# Digital_Output_LED_Monitor.net
KiCad netlist of a schematic drawn in Altium Designer
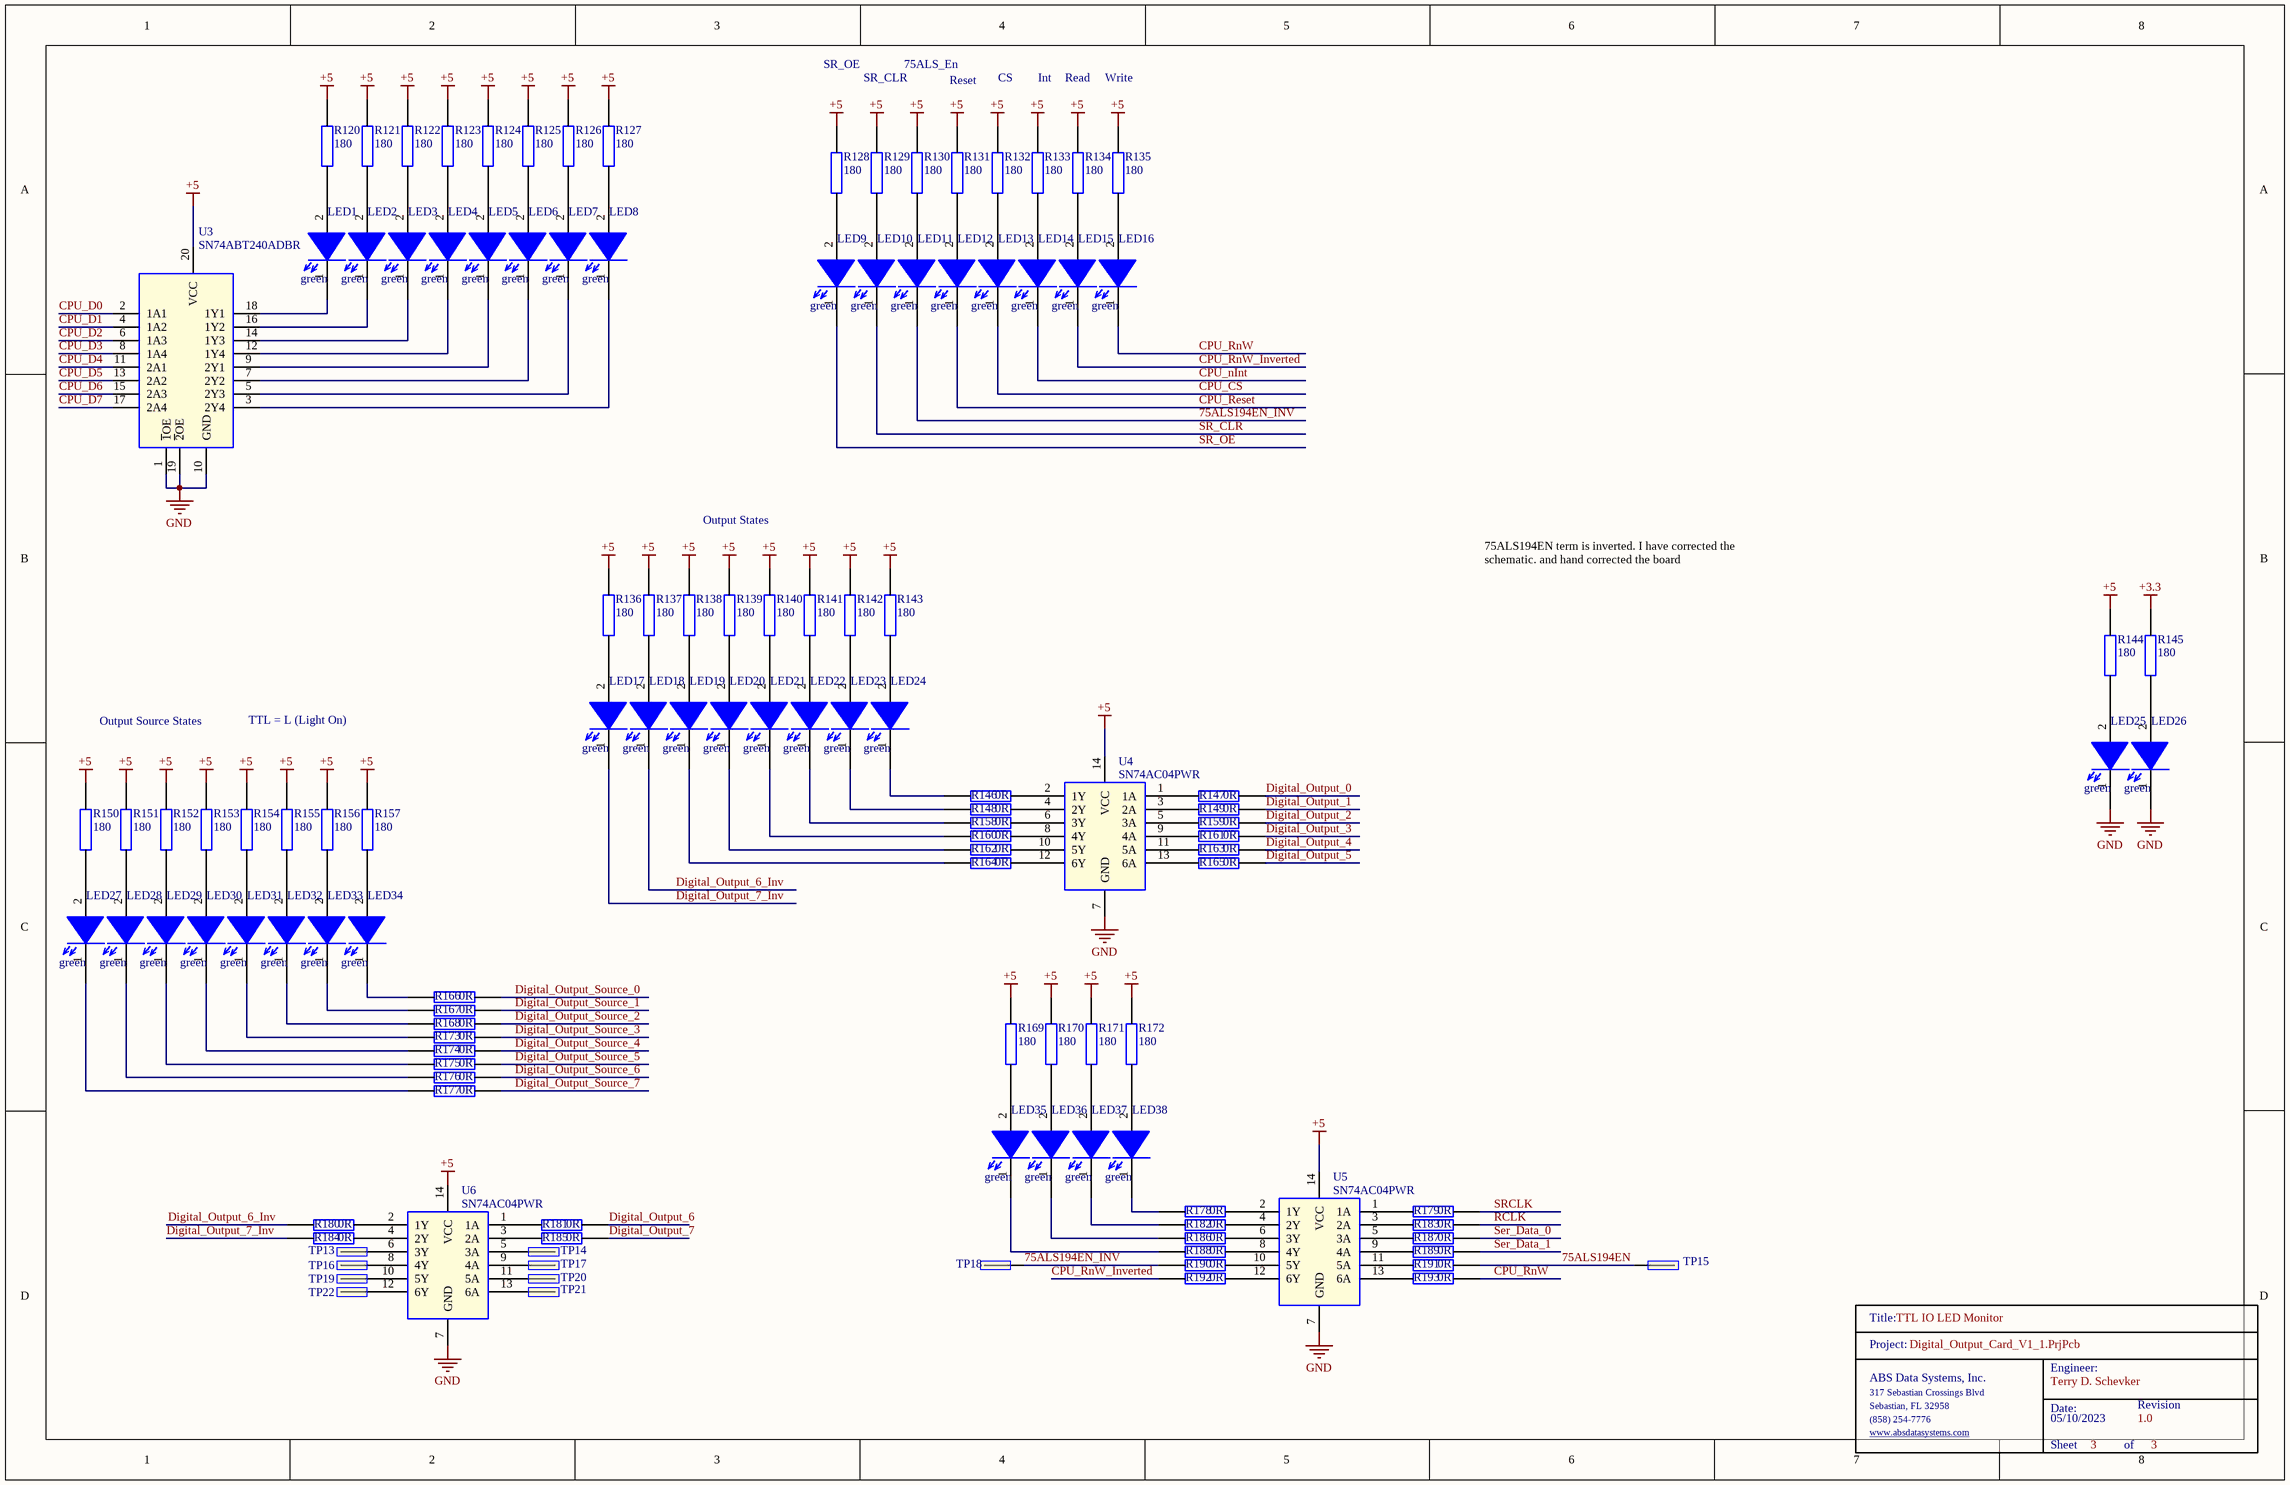
[diagram p0: Digital_Output_LED_Monitor.SchDoc]

(export (version "E")
  (design (tool "Eeschema 10.0.6"))
  (components
    (comp (ref "LED1")
      (value "green")
      (footprint "0603_Diode")
      (description "Wurth Elektronik 0603 green")
      (fields
        (field (name "MANUFACTURER") "Wurth Electronics")
        (field (name "MANUFACTURER PART NUMBER") "150060GS75000")
      )
      (libsource (lib "Misc") (part "150060GS75000"))
    )
    (comp (ref "LED2")
      (value "green")
      (footprint "0603_Diode")
      (description "Wurth Elektronik 0603 green")
      (fields
        (field (name "MANUFACTURER") "Wurth Electronics")
        (field (name "MANUFACTURER PART NUMBER") "150060GS75000")
      )
      (libsource (lib "Misc") (part "150060GS75000"))
    )
    (comp (ref "LED3")
      (value "green")
      (footprint "0603_Diode")
      (description "Wurth Elektronik 0603 green")
      (fields
        (field (name "MANUFACTURER") "Wurth Electronics")
        (field (name "MANUFACTURER PART NUMBER") "150060GS75000")
      )
      (libsource (lib "Misc") (part "150060GS75000"))
    )
    (comp (ref "LED4")
      (value "green")
      (footprint "0603_Diode")
      (description "Wurth Elektronik 0603 green")
      (fields
        (field (name "MANUFACTURER") "Wurth Electronics")
        (field (name "MANUFACTURER PART NUMBER") "150060GS75000")
      )
      (libsource (lib "Misc") (part "150060GS75000"))
    )
    (comp (ref "LED5")
      (value "green")
      (footprint "0603_Diode")
      (description "Wurth Elektronik 0603 green")
      (fields
        (field (name "MANUFACTURER") "Wurth Electronics")
        (field (name "MANUFACTURER PART NUMBER") "150060GS75000")
      )
      (libsource (lib "Misc") (part "150060GS75000"))
    )
    (comp (ref "LED6")
      (value "green")
      (footprint "0603_Diode")
      (description "Wurth Elektronik 0603 green")
      (fields
        (field (name "MANUFACTURER") "Wurth Electronics")
        (field (name "MANUFACTURER PART NUMBER") "150060GS75000")
      )
      (libsource (lib "Misc") (part "150060GS75000"))
    )
    (comp (ref "LED7")
      (value "green")
      (footprint "0603_Diode")
      (description "Wurth Elektronik 0603 green")
      (fields
        (field (name "MANUFACTURER") "Wurth Electronics")
        (field (name "MANUFACTURER PART NUMBER") "150060GS75000")
      )
      (libsource (lib "Misc") (part "150060GS75000"))
    )
    (comp (ref "LED8")
      (value "green")
      (footprint "0603_Diode")
      (description "Wurth Elektronik 0603 green")
      (fields
        (field (name "MANUFACTURER") "Wurth Electronics")
        (field (name "MANUFACTURER PART NUMBER") "150060GS75000")
      )
      (libsource (lib "Misc") (part "150060GS75000"))
    )
    (comp (ref "LED9")
      (value "green")
      (footprint "0603_Diode")
      (description "Wurth Elektronik 0603 green")
      (fields
        (field (name "MANUFACTURER") "Wurth Electronics")
        (field (name "MANUFACTURER PART NUMBER") "150060GS75000")
      )
      (libsource (lib "Misc") (part "150060GS75000"))
    )
    (comp (ref "LED10")
      (value "green")
      (footprint "0603_Diode")
      (description "Wurth Elektronik 0603 green")
      (fields
        (field (name "MANUFACTURER") "Wurth Electronics")
        (field (name "MANUFACTURER PART NUMBER") "150060GS75000")
      )
      (libsource (lib "Misc") (part "150060GS75000"))
    )
    (comp (ref "LED11")
      (value "green")
      (footprint "0603_Diode")
      (description "Wurth Elektronik 0603 green")
      (fields
        (field (name "MANUFACTURER") "Wurth Electronics")
        (field (name "MANUFACTURER PART NUMBER") "150060GS75000")
      )
      (libsource (lib "Misc") (part "150060GS75000"))
    )
    (comp (ref "LED12")
      (value "green")
      (footprint "0603_Diode")
      (description "Wurth Elektronik 0603 green")
      (fields
        (field (name "MANUFACTURER") "Wurth Electronics")
        (field (name "MANUFACTURER PART NUMBER") "150060GS75000")
      )
      (libsource (lib "Misc") (part "150060GS75000"))
    )
    (comp (ref "LED13")
      (value "green")
      (footprint "0603_Diode")
      (description "Wurth Elektronik 0603 green")
      (fields
        (field (name "MANUFACTURER") "Wurth Electronics")
        (field (name "MANUFACTURER PART NUMBER") "150060GS75000")
      )
      (libsource (lib "Misc") (part "150060GS75000"))
    )
    (comp (ref "LED14")
      (value "green")
      (footprint "0603_Diode")
      (description "Wurth Elektronik 0603 green")
      (fields
        (field (name "MANUFACTURER") "Wurth Electronics")
        (field (name "MANUFACTURER PART NUMBER") "150060GS75000")
      )
      (libsource (lib "Misc") (part "150060GS75000"))
    )
    (comp (ref "LED15")
      (value "green")
      (footprint "0603_Diode")
      (description "Wurth Elektronik 0603 green")
      (fields
        (field (name "MANUFACTURER") "Wurth Electronics")
        (field (name "MANUFACTURER PART NUMBER") "150060GS75000")
      )
      (libsource (lib "Misc") (part "150060GS75000"))
    )
    (comp (ref "LED16")
      (value "green")
      (footprint "0603_Diode")
      (description "Wurth Elektronik 0603 green")
      (fields
        (field (name "MANUFACTURER") "Wurth Electronics")
        (field (name "MANUFACTURER PART NUMBER") "150060GS75000")
      )
      (libsource (lib "Misc") (part "150060GS75000"))
    )
    (comp (ref "LED17")
      (value "green")
      (footprint "0603_Diode")
      (description "Wurth Elektronik 0603 green")
      (fields
        (field (name "MANUFACTURER") "Wurth Electronics")
        (field (name "MANUFACTURER PART NUMBER") "150060GS75000")
      )
      (libsource (lib "Misc") (part "150060GS75000"))
    )
    (comp (ref "LED18")
      (value "green")
      (footprint "0603_Diode")
      (description "Wurth Elektronik 0603 green")
      (fields
        (field (name "MANUFACTURER") "Wurth Electronics")
        (field (name "MANUFACTURER PART NUMBER") "150060GS75000")
      )
      (libsource (lib "Misc") (part "150060GS75000"))
    )
    (comp (ref "LED19")
      (value "green")
      (footprint "0603_Diode")
      (description "Wurth Elektronik 0603 green")
      (fields
        (field (name "MANUFACTURER") "Wurth Electronics")
        (field (name "MANUFACTURER PART NUMBER") "150060GS75000")
      )
      (libsource (lib "Misc") (part "150060GS75000"))
    )
    (comp (ref "LED20")
      (value "green")
      (footprint "0603_Diode")
      (description "Wurth Elektronik 0603 green")
      (fields
        (field (name "MANUFACTURER") "Wurth Electronics")
        (field (name "MANUFACTURER PART NUMBER") "150060GS75000")
      )
      (libsource (lib "Misc") (part "150060GS75000"))
    )
    (comp (ref "LED21")
      (value "green")
      (footprint "0603_Diode")
      (description "Wurth Elektronik 0603 green")
      (fields
        (field (name "MANUFACTURER") "Wurth Electronics")
        (field (name "MANUFACTURER PART NUMBER") "150060GS75000")
      )
      (libsource (lib "Misc") (part "150060GS75000"))
    )
    (comp (ref "LED22")
      (value "green")
      (footprint "0603_Diode")
      (description "Wurth Elektronik 0603 green")
      (fields
        (field (name "MANUFACTURER") "Wurth Electronics")
        (field (name "MANUFACTURER PART NUMBER") "150060GS75000")
      )
      (libsource (lib "Misc") (part "150060GS75000"))
    )
    (comp (ref "LED23")
      (value "green")
      (footprint "0603_Diode")
      (description "Wurth Elektronik 0603 green")
      (fields
        (field (name "MANUFACTURER") "Wurth Electronics")
        (field (name "MANUFACTURER PART NUMBER") "150060GS75000")
      )
      (libsource (lib "Misc") (part "150060GS75000"))
    )
    (comp (ref "LED24")
      (value "green")
      (footprint "0603_Diode")
      (description "Wurth Elektronik 0603 green")
      (fields
        (field (name "MANUFACTURER") "Wurth Electronics")
        (field (name "MANUFACTURER PART NUMBER") "150060GS75000")
      )
      (libsource (lib "Misc") (part "150060GS75000"))
    )
    (comp (ref "LED25")
      (value "green")
      (footprint "0603_Diode")
      (description "Wurth Elektronik 0603 green")
      (fields
        (field (name "MANUFACTURER") "Wurth Electronics")
        (field (name "MANUFACTURER PART NUMBER") "150060GS75000")
      )
      (libsource (lib "Misc") (part "150060GS75000"))
    )
    (comp (ref "LED26")
      (value "green")
      (footprint "0603_Diode")
      (description "Wurth Elektronik 0603 green")
      (fields
        (field (name "MANUFACTURER") "Wurth Electronics")
        (field (name "MANUFACTURER PART NUMBER") "150060GS75000")
      )
      (libsource (lib "Misc") (part "150060GS75000"))
    )
    (comp (ref "LED27")
      (value "green")
      (footprint "0603_Diode")
      (description "Wurth Elektronik 0603 green")
      (fields
        (field (name "MANUFACTURER") "Wurth Electronics")
        (field (name "MANUFACTURER PART NUMBER") "150060GS75000")
      )
      (libsource (lib "Misc") (part "150060GS75000"))
    )
    (comp (ref "LED28")
      (value "green")
      (footprint "0603_Diode")
      (description "Wurth Elektronik 0603 green")
      (fields
        (field (name "MANUFACTURER") "Wurth Electronics")
        (field (name "MANUFACTURER PART NUMBER") "150060GS75000")
      )
      (libsource (lib "Misc") (part "150060GS75000"))
    )
    (comp (ref "LED29")
      (value "green")
      (footprint "0603_Diode")
      (description "Wurth Elektronik 0603 green")
      (fields
        (field (name "MANUFACTURER") "Wurth Electronics")
        (field (name "MANUFACTURER PART NUMBER") "150060GS75000")
      )
      (libsource (lib "Misc") (part "150060GS75000"))
    )
    (comp (ref "LED30")
      (value "green")
      (footprint "0603_Diode")
      (description "Wurth Elektronik 0603 green")
      (fields
        (field (name "MANUFACTURER") "Wurth Electronics")
        (field (name "MANUFACTURER PART NUMBER") "150060GS75000")
      )
      (libsource (lib "Misc") (part "150060GS75000"))
    )
    (comp (ref "LED31")
      (value "green")
      (footprint "0603_Diode")
      (description "Wurth Elektronik 0603 green")
      (fields
        (field (name "MANUFACTURER") "Wurth Electronics")
        (field (name "MANUFACTURER PART NUMBER") "150060GS75000")
      )
      (libsource (lib "Misc") (part "150060GS75000"))
    )
    (comp (ref "LED32")
      (value "green")
      (footprint "0603_Diode")
      (description "Wurth Elektronik 0603 green")
      (fields
        (field (name "MANUFACTURER") "Wurth Electronics")
        (field (name "MANUFACTURER PART NUMBER") "150060GS75000")
      )
      (libsource (lib "Misc") (part "150060GS75000"))
    )
    (comp (ref "LED33")
      (value "green")
      (footprint "0603_Diode")
      (description "Wurth Elektronik 0603 green")
      (fields
        (field (name "MANUFACTURER") "Wurth Electronics")
        (field (name "MANUFACTURER PART NUMBER") "150060GS75000")
      )
      (libsource (lib "Misc") (part "150060GS75000"))
    )
    (comp (ref "LED34")
      (value "green")
      (footprint "0603_Diode")
      (description "Wurth Elektronik 0603 green")
      (fields
        (field (name "MANUFACTURER") "Wurth Electronics")
        (field (name "MANUFACTURER PART NUMBER") "150060GS75000")
      )
      (libsource (lib "Misc") (part "150060GS75000"))
    )
    (comp (ref "LED35")
      (value "green")
      (footprint "0603_Diode")
      (description "Wurth Elektronik 0603 green")
      (fields
        (field (name "MANUFACTURER") "Wurth Electronics")
        (field (name "MANUFACTURER PART NUMBER") "150060GS75000")
      )
      (libsource (lib "Misc") (part "150060GS75000"))
    )
    (comp (ref "LED36")
      (value "green")
      (footprint "0603_Diode")
      (description "Wurth Elektronik 0603 green")
      (fields
        (field (name "MANUFACTURER") "Wurth Electronics")
        (field (name "MANUFACTURER PART NUMBER") "150060GS75000")
      )
      (libsource (lib "Misc") (part "150060GS75000"))
    )
    (comp (ref "LED37")
      (value "green")
      (footprint "0603_Diode")
      (description "Wurth Elektronik 0603 green")
      (fields
        (field (name "MANUFACTURER") "Wurth Electronics")
        (field (name "MANUFACTURER PART NUMBER") "150060GS75000")
      )
      (libsource (lib "Misc") (part "150060GS75000"))
    )
    (comp (ref "LED38")
      (value "green")
      (footprint "0603_Diode")
      (description "Wurth Elektronik 0603 green")
      (fields
        (field (name "MANUFACTURER") "Wurth Electronics")
        (field (name "MANUFACTURER PART NUMBER") "150060GS75000")
      )
      (libsource (lib "Misc") (part "150060GS75000"))
    )
    (comp (ref "R120")
      (value "180")
      (footprint "0603")
      (description "YAGEO 0603 180 ohm")
      (fields
        (field (name "MOUSER PART NUMBER") "603-RC0603JR-070RL")
        (field (name "MANUFACTURER_PART_NUMBER") "RC0603JR-070RL")
      )
      (libsource (lib "Resistors") (part "RC0603FR-13180RL"))
    )
    (comp (ref "R121")
      (value "180")
      (footprint "0603")
      (description "YAGEO 0603 180 ohm")
      (fields
        (field (name "MOUSER PART NUMBER") "603-RC0603JR-070RL")
        (field (name "MANUFACTURER_PART_NUMBER") "RC0603JR-070RL")
      )
      (libsource (lib "Resistors") (part "RC0603FR-13180RL"))
    )
    (comp (ref "R122")
      (value "180")
      (footprint "0603")
      (description "YAGEO 0603 180 ohm")
      (fields
        (field (name "MOUSER PART NUMBER") "603-RC0603JR-070RL")
        (field (name "MANUFACTURER_PART_NUMBER") "RC0603JR-070RL")
      )
      (libsource (lib "Resistors") (part "RC0603FR-13180RL"))
    )
    (comp (ref "R123")
      (value "180")
      (footprint "0603")
      (description "YAGEO 0603 180 ohm")
      (fields
        (field (name "MOUSER PART NUMBER") "603-RC0603JR-070RL")
        (field (name "MANUFACTURER_PART_NUMBER") "RC0603JR-070RL")
      )
      (libsource (lib "Resistors") (part "RC0603FR-13180RL"))
    )
    (comp (ref "R124")
      (value "180")
      (footprint "0603")
      (description "YAGEO 0603 180 ohm")
      (fields
        (field (name "MOUSER PART NUMBER") "603-RC0603JR-070RL")
        (field (name "MANUFACTURER_PART_NUMBER") "RC0603JR-070RL")
      )
      (libsource (lib "Resistors") (part "RC0603FR-13180RL"))
    )
    (comp (ref "R125")
      (value "180")
      (footprint "0603")
      (description "YAGEO 0603 180 ohm")
      (fields
        (field (name "MOUSER PART NUMBER") "603-RC0603JR-070RL")
        (field (name "MANUFACTURER_PART_NUMBER") "RC0603JR-070RL")
      )
      (libsource (lib "Resistors") (part "RC0603FR-13180RL"))
    )
    (comp (ref "R126")
      (value "180")
      (footprint "0603")
      (description "YAGEO 0603 180 ohm")
      (fields
        (field (name "MOUSER PART NUMBER") "603-RC0603JR-070RL")
        (field (name "MANUFACTURER_PART_NUMBER") "RC0603JR-070RL")
      )
      (libsource (lib "Resistors") (part "RC0603FR-13180RL"))
    )
    (comp (ref "R127")
      (value "180")
      (footprint "0603")
      (description "YAGEO 0603 180 ohm")
      (fields
        (field (name "MOUSER PART NUMBER") "603-RC0603JR-070RL")
        (field (name "MANUFACTURER_PART_NUMBER") "RC0603JR-070RL")
      )
      (libsource (lib "Resistors") (part "RC0603FR-13180RL"))
    )
    (comp (ref "R128")
      (value "180")
      (footprint "0603")
      (description "YAGEO 0603 180 ohm")
      (fields
        (field (name "MOUSER PART NUMBER") "603-RC0603JR-070RL")
        (field (name "MANUFACTURER_PART_NUMBER") "RC0603JR-070RL")
      )
      (libsource (lib "Resistors") (part "RC0603FR-13180RL"))
    )
    (comp (ref "R129")
      (value "180")
      (footprint "0603")
      (description "YAGEO 0603 180 ohm")
      (fields
        (field (name "MOUSER PART NUMBER") "603-RC0603JR-070RL")
        (field (name "MANUFACTURER_PART_NUMBER") "RC0603JR-070RL")
      )
      (libsource (lib "Resistors") (part "RC0603FR-13180RL"))
    )
    (comp (ref "R130")
      (value "180")
      (footprint "0603")
      (description "YAGEO 0603 180 ohm")
      (fields
        (field (name "MOUSER PART NUMBER") "603-RC0603JR-070RL")
        (field (name "MANUFACTURER_PART_NUMBER") "RC0603JR-070RL")
      )
      (libsource (lib "Resistors") (part "RC0603FR-13180RL"))
    )
    (comp (ref "R131")
      (value "180")
      (footprint "0603")
      (description "YAGEO 0603 180 ohm")
      (fields
        (field (name "MOUSER PART NUMBER") "603-RC0603JR-070RL")
        (field (name "MANUFACTURER_PART_NUMBER") "RC0603JR-070RL")
      )
      (libsource (lib "Resistors") (part "RC0603FR-13180RL"))
    )
    (comp (ref "R132")
      (value "180")
      (footprint "0603")
      (description "YAGEO 0603 180 ohm")
      (fields
        (field (name "MOUSER PART NUMBER") "603-RC0603JR-070RL")
        (field (name "MANUFACTURER_PART_NUMBER") "RC0603JR-070RL")
      )
      (libsource (lib "Resistors") (part "RC0603FR-13180RL"))
    )
    (comp (ref "R133")
      (value "180")
      (footprint "0603")
      (description "YAGEO 0603 180 ohm")
      (fields
        (field (name "MOUSER PART NUMBER") "603-RC0603JR-070RL")
        (field (name "MANUFACTURER_PART_NUMBER") "RC0603JR-070RL")
      )
      (libsource (lib "Resistors") (part "RC0603FR-13180RL"))
    )
    (comp (ref "R134")
      (value "180")
      (footprint "0603")
      (description "YAGEO 0603 180 ohm")
      (fields
        (field (name "MOUSER PART NUMBER") "603-RC0603JR-070RL")
        (field (name "MANUFACTURER_PART_NUMBER") "RC0603JR-070RL")
      )
      (libsource (lib "Resistors") (part "RC0603FR-13180RL"))
    )
    (comp (ref "R135")
      (value "180")
      (footprint "0603")
      (description "YAGEO 0603 180 ohm")
      (fields
        (field (name "MOUSER PART NUMBER") "603-RC0603JR-070RL")
        (field (name "MANUFACTURER_PART_NUMBER") "RC0603JR-070RL")
      )
      (libsource (lib "Resistors") (part "RC0603FR-13180RL"))
    )
    (comp (ref "R136")
      (value "180")
      (footprint "0603")
      (description "YAGEO 0603 180 ohm")
      (fields
        (field (name "MOUSER PART NUMBER") "603-RC0603JR-070RL")
        (field (name "MANUFACTURER_PART_NUMBER") "RC0603JR-070RL")
      )
      (libsource (lib "Resistors") (part "RC0603FR-13180RL"))
    )
    (comp (ref "R137")
      (value "180")
      (footprint "0603")
      (description "YAGEO 0603 180 ohm")
      (fields
        (field (name "MOUSER PART NUMBER") "603-RC0603JR-070RL")
        (field (name "MANUFACTURER_PART_NUMBER") "RC0603JR-070RL")
      )
      (libsource (lib "Resistors") (part "RC0603FR-13180RL"))
    )
    (comp (ref "R138")
      (value "180")
      (footprint "0603")
      (description "YAGEO 0603 180 ohm")
      (fields
        (field (name "MOUSER PART NUMBER") "603-RC0603JR-070RL")
        (field (name "MANUFACTURER_PART_NUMBER") "RC0603JR-070RL")
      )
      (libsource (lib "Resistors") (part "RC0603FR-13180RL"))
    )
    (comp (ref "R139")
      (value "180")
      (footprint "0603")
      (description "YAGEO 0603 180 ohm")
      (fields
        (field (name "MOUSER PART NUMBER") "603-RC0603JR-070RL")
        (field (name "MANUFACTURER_PART_NUMBER") "RC0603JR-070RL")
      )
      (libsource (lib "Resistors") (part "RC0603FR-13180RL"))
    )
    (comp (ref "R140")
      (value "180")
      (footprint "0603")
      (description "YAGEO 0603 180 ohm")
      (fields
        (field (name "MOUSER PART NUMBER") "603-RC0603JR-070RL")
        (field (name "MANUFACTURER_PART_NUMBER") "RC0603JR-070RL")
      )
      (libsource (lib "Resistors") (part "RC0603FR-13180RL"))
    )
    (comp (ref "R141")
      (value "180")
      (footprint "0603")
      (description "YAGEO 0603 180 ohm")
      (fields
        (field (name "MOUSER PART NUMBER") "603-RC0603JR-070RL")
        (field (name "MANUFACTURER_PART_NUMBER") "RC0603JR-070RL")
      )
      (libsource (lib "Resistors") (part "RC0603FR-13180RL"))
    )
    (comp (ref "R142")
      (value "180")
      (footprint "0603")
      (description "YAGEO 0603 180 ohm")
      (fields
        (field (name "MOUSER PART NUMBER") "603-RC0603JR-070RL")
        (field (name "MANUFACTURER_PART_NUMBER") "RC0603JR-070RL")
      )
      (libsource (lib "Resistors") (part "RC0603FR-13180RL"))
    )
    (comp (ref "R143")
      (value "180")
      (footprint "0603")
      (description "YAGEO 0603 180 ohm")
      (fields
        (field (name "MOUSER PART NUMBER") "603-RC0603JR-070RL")
        (field (name "MANUFACTURER_PART_NUMBER") "RC0603JR-070RL")
      )
      (libsource (lib "Resistors") (part "RC0603FR-13180RL"))
    )
    (comp (ref "R144")
      (value "180")
      (footprint "0603")
      (description "YAGEO 0603 180 ohm")
      (fields
        (field (name "MOUSER PART NUMBER") "603-RC0603JR-070RL")
        (field (name "MANUFACTURER_PART_NUMBER") "RC0603JR-070RL")
      )
      (libsource (lib "Resistors") (part "RC0603FR-13180RL"))
    )
    (comp (ref "R145")
      (value "180")
      (footprint "0603")
      (description "YAGEO 0603 180 ohm")
      (fields
        (field (name "MOUSER PART NUMBER") "603-RC0603JR-070RL")
        (field (name "MANUFACTURER_PART_NUMBER") "RC0603JR-070RL")
      )
      (libsource (lib "Resistors") (part "RC0603FR-13180RL"))
    )
    (comp (ref "R146")
      (value "0R")
      (footprint "0603")
      (description "YAGEO 0603 0 ohm")
      (fields
        (field (name "MOUSER PART NUMBER") "603-RC0603JR-070RL")
        (field (name "MANUFACTURER_PART_NUMBER") "RC0603JR-070RL")
      )
      (libsource (lib "Resistors") (part "RC0603JR-070RL"))
    )
    (comp (ref "R147")
      (value "0R")
      (footprint "0603")
      (description "YAGEO 0603 0 ohm")
      (fields
        (field (name "MOUSER PART NUMBER") "603-RC0603JR-070RL")
        (field (name "MANUFACTURER_PART_NUMBER") "RC0603JR-070RL")
      )
      (libsource (lib "Resistors") (part "RC0603JR-070RL"))
    )
    (comp (ref "R148")
      (value "0R")
      (footprint "0603")
      (description "YAGEO 0603 0 ohm")
      (fields
        (field (name "MOUSER PART NUMBER") "603-RC0603JR-070RL")
        (field (name "MANUFACTURER_PART_NUMBER") "RC0603JR-070RL")
      )
      (libsource (lib "Resistors") (part "RC0603JR-070RL"))
    )
    (comp (ref "R149")
      (value "0R")
      (footprint "0603")
      (description "YAGEO 0603 0 ohm")
      (fields
        (field (name "MOUSER PART NUMBER") "603-RC0603JR-070RL")
        (field (name "MANUFACTURER_PART_NUMBER") "RC0603JR-070RL")
      )
      (libsource (lib "Resistors") (part "RC0603JR-070RL"))
    )
    (comp (ref "R150")
      (value "180")
      (footprint "0603")
      (description "YAGEO 0603 180 ohm")
      (fields
        (field (name "MOUSER PART NUMBER") "603-RC0603JR-070RL")
        (field (name "MANUFACTURER_PART_NUMBER") "RC0603JR-070RL")
      )
      (libsource (lib "Resistors") (part "RC0603FR-13180RL"))
    )
    (comp (ref "R151")
      (value "180")
      (footprint "0603")
      (description "YAGEO 0603 180 ohm")
      (fields
        (field (name "MOUSER PART NUMBER") "603-RC0603JR-070RL")
        (field (name "MANUFACTURER_PART_NUMBER") "RC0603JR-070RL")
      )
      (libsource (lib "Resistors") (part "RC0603FR-13180RL"))
    )
    (comp (ref "R152")
      (value "180")
      (footprint "0603")
      (description "YAGEO 0603 180 ohm")
      (fields
        (field (name "MOUSER PART NUMBER") "603-RC0603JR-070RL")
        (field (name "MANUFACTURER_PART_NUMBER") "RC0603JR-070RL")
      )
      (libsource (lib "Resistors") (part "RC0603FR-13180RL"))
    )
    (comp (ref "R153")
      (value "180")
      (footprint "0603")
      (description "YAGEO 0603 180 ohm")
      (fields
        (field (name "MOUSER PART NUMBER") "603-RC0603JR-070RL")
        (field (name "MANUFACTURER_PART_NUMBER") "RC0603JR-070RL")
      )
      (libsource (lib "Resistors") (part "RC0603FR-13180RL"))
    )
    (comp (ref "R154")
      (value "180")
      (footprint "0603")
      (description "YAGEO 0603 180 ohm")
      (fields
        (field (name "MOUSER PART NUMBER") "603-RC0603JR-070RL")
        (field (name "MANUFACTURER_PART_NUMBER") "RC0603JR-070RL")
      )
      (libsource (lib "Resistors") (part "RC0603FR-13180RL"))
    )
    (comp (ref "R155")
      (value "180")
      (footprint "0603")
      (description "YAGEO 0603 180 ohm")
      (fields
        (field (name "MOUSER PART NUMBER") "603-RC0603JR-070RL")
        (field (name "MANUFACTURER_PART_NUMBER") "RC0603JR-070RL")
      )
      (libsource (lib "Resistors") (part "RC0603FR-13180RL"))
    )
    (comp (ref "R156")
      (value "180")
      (footprint "0603")
      (description "YAGEO 0603 180 ohm")
      (fields
        (field (name "MOUSER PART NUMBER") "603-RC0603JR-070RL")
        (field (name "MANUFACTURER_PART_NUMBER") "RC0603JR-070RL")
      )
      (libsource (lib "Resistors") (part "RC0603FR-13180RL"))
    )
    (comp (ref "R157")
      (value "180")
      (footprint "0603")
      (description "YAGEO 0603 180 ohm")
      (fields
        (field (name "MOUSER PART NUMBER") "603-RC0603JR-070RL")
        (field (name "MANUFACTURER_PART_NUMBER") "RC0603JR-070RL")
      )
      (libsource (lib "Resistors") (part "RC0603FR-13180RL"))
    )
    (comp (ref "R158")
      (value "0R")
      (footprint "0603")
      (description "YAGEO 0603 0 ohm")
      (fields
        (field (name "MOUSER PART NUMBER") "603-RC0603JR-070RL")
        (field (name "MANUFACTURER_PART_NUMBER") "RC0603JR-070RL")
      )
      (libsource (lib "Resistors") (part "RC0603JR-070RL"))
    )
    (comp (ref "R159")
      (value "0R")
      (footprint "0603")
      (description "YAGEO 0603 0 ohm")
      (fields
        (field (name "MOUSER PART NUMBER") "603-RC0603JR-070RL")
        (field (name "MANUFACTURER_PART_NUMBER") "RC0603JR-070RL")
      )
      (libsource (lib "Resistors") (part "RC0603JR-070RL"))
    )
    (comp (ref "R160")
      (value "0R")
      (footprint "0603")
      (description "YAGEO 0603 0 ohm")
      (fields
        (field (name "MOUSER PART NUMBER") "603-RC0603JR-070RL")
        (field (name "MANUFACTURER_PART_NUMBER") "RC0603JR-070RL")
      )
      (libsource (lib "Resistors") (part "RC0603JR-070RL"))
    )
    (comp (ref "R161")
      (value "0R")
      (footprint "0603")
      (description "YAGEO 0603 0 ohm")
      (fields
        (field (name "MOUSER PART NUMBER") "603-RC0603JR-070RL")
        (field (name "MANUFACTURER_PART_NUMBER") "RC0603JR-070RL")
      )
      (libsource (lib "Resistors") (part "RC0603JR-070RL"))
    )
    (comp (ref "R162")
      (value "0R")
      (footprint "0603")
      (description "YAGEO 0603 0 ohm")
      (fields
        (field (name "MOUSER PART NUMBER") "603-RC0603JR-070RL")
        (field (name "MANUFACTURER_PART_NUMBER") "RC0603JR-070RL")
      )
      (libsource (lib "Resistors") (part "RC0603JR-070RL"))
    )
    (comp (ref "R163")
      (value "0R")
      (footprint "0603")
      (description "YAGEO 0603 0 ohm")
      (fields
        (field (name "MOUSER PART NUMBER") "603-RC0603JR-070RL")
        (field (name "MANUFACTURER_PART_NUMBER") "RC0603JR-070RL")
      )
      (libsource (lib "Resistors") (part "RC0603JR-070RL"))
    )
    (comp (ref "R164")
      (value "0R")
      (footprint "0603")
      (description "YAGEO 0603 0 ohm")
      (fields
        (field (name "MOUSER PART NUMBER") "603-RC0603JR-070RL")
        (field (name "MANUFACTURER_PART_NUMBER") "RC0603JR-070RL")
      )
      (libsource (lib "Resistors") (part "RC0603JR-070RL"))
    )
    (comp (ref "R165")
      (value "0R")
      (footprint "0603")
      (description "YAGEO 0603 0 ohm")
      (fields
        (field (name "MOUSER PART NUMBER") "603-RC0603JR-070RL")
        (field (name "MANUFACTURER_PART_NUMBER") "RC0603JR-070RL")
      )
      (libsource (lib "Resistors") (part "RC0603JR-070RL"))
    )
    (comp (ref "R166")
      (value "0R")
      (footprint "0603")
      (description "YAGEO 0603 0 ohm")
      (fields
        (field (name "MOUSER PART NUMBER") "603-RC0603JR-070RL")
        (field (name "MANUFACTURER_PART_NUMBER") "RC0603JR-070RL")
      )
      (libsource (lib "Resistors") (part "RC0603JR-070RL"))
    )
    (comp (ref "R167")
      (value "0R")
      (footprint "0603")
      (description "YAGEO 0603 0 ohm")
      (fields
        (field (name "MOUSER PART NUMBER") "603-RC0603JR-070RL")
        (field (name "MANUFACTURER_PART_NUMBER") "RC0603JR-070RL")
      )
      (libsource (lib "Resistors") (part "RC0603JR-070RL"))
    )
    (comp (ref "R168")
      (value "0R")
      (footprint "0603")
      (description "YAGEO 0603 0 ohm")
      (fields
        (field (name "MOUSER PART NUMBER") "603-RC0603JR-070RL")
        (field (name "MANUFACTURER_PART_NUMBER") "RC0603JR-070RL")
      )
      (libsource (lib "Resistors") (part "RC0603JR-070RL"))
    )
    (comp (ref "R169")
      (value "180")
      (footprint "0603")
      (description "YAGEO 0603 180 ohm")
      (fields
        (field (name "MOUSER PART NUMBER") "603-RC0603JR-070RL")
        (field (name "MANUFACTURER_PART_NUMBER") "RC0603JR-070RL")
      )
      (libsource (lib "Resistors") (part "RC0603FR-13180RL"))
    )
    (comp (ref "R170")
      (value "180")
      (footprint "0603")
      (description "YAGEO 0603 180 ohm")
      (fields
        (field (name "MOUSER PART NUMBER") "603-RC0603JR-070RL")
        (field (name "MANUFACTURER_PART_NUMBER") "RC0603JR-070RL")
      )
      (libsource (lib "Resistors") (part "RC0603FR-13180RL"))
    )
    (comp (ref "R171")
      (value "180")
      (footprint "0603")
      (description "YAGEO 0603 180 ohm")
      (fields
        (field (name "MOUSER PART NUMBER") "603-RC0603JR-070RL")
        (field (name "MANUFACTURER_PART_NUMBER") "RC0603JR-070RL")
      )
      (libsource (lib "Resistors") (part "RC0603FR-13180RL"))
    )
    (comp (ref "R172")
      (value "180")
      (footprint "0603")
      (description "YAGEO 0603 180 ohm")
      (fields
        (field (name "MOUSER PART NUMBER") "603-RC0603JR-070RL")
        (field (name "MANUFACTURER_PART_NUMBER") "RC0603JR-070RL")
      )
      (libsource (lib "Resistors") (part "RC0603FR-13180RL"))
    )
    (comp (ref "R173")
      (value "0R")
      (footprint "0603")
      (description "YAGEO 0603 0 ohm")
      (fields
        (field (name "MOUSER PART NUMBER") "603-RC0603JR-070RL")
        (field (name "MANUFACTURER_PART_NUMBER") "RC0603JR-070RL")
      )
      (libsource (lib "Resistors") (part "RC0603JR-070RL"))
    )
    (comp (ref "R174")
      (value "0R")
      (footprint "0603")
      (description "YAGEO 0603 0 ohm")
      (fields
        (field (name "MOUSER PART NUMBER") "603-RC0603JR-070RL")
        (field (name "MANUFACTURER_PART_NUMBER") "RC0603JR-070RL")
      )
      (libsource (lib "Resistors") (part "RC0603JR-070RL"))
    )
    (comp (ref "R175")
      (value "0R")
      (footprint "0603")
      (description "YAGEO 0603 0 ohm")
      (fields
        (field (name "MOUSER PART NUMBER") "603-RC0603JR-070RL")
        (field (name "MANUFACTURER_PART_NUMBER") "RC0603JR-070RL")
      )
      (libsource (lib "Resistors") (part "RC0603JR-070RL"))
    )
    (comp (ref "R176")
      (value "0R")
      (footprint "0603")
      (description "YAGEO 0603 0 ohm")
      (fields
        (field (name "MOUSER PART NUMBER") "603-RC0603JR-070RL")
        (field (name "MANUFACTURER_PART_NUMBER") "RC0603JR-070RL")
      )
      (libsource (lib "Resistors") (part "RC0603JR-070RL"))
    )
    (comp (ref "R177")
      (value "0R")
      (footprint "0603")
      (description "YAGEO 0603 0 ohm")
      (fields
        (field (name "MOUSER PART NUMBER") "603-RC0603JR-070RL")
        (field (name "MANUFACTURER_PART_NUMBER") "RC0603JR-070RL")
      )
      (libsource (lib "Resistors") (part "RC0603JR-070RL"))
    )
    (comp (ref "R178")
      (value "0R")
      (footprint "0603")
      (description "YAGEO 0603 0 ohm")
      (fields
        (field (name "MOUSER PART NUMBER") "603-RC0603JR-070RL")
        (field (name "MANUFACTURER_PART_NUMBER") "RC0603JR-070RL")
      )
      (libsource (lib "Resistors") (part "RC0603JR-070RL"))
    )
    (comp (ref "R179")
      (value "0R")
      (footprint "0603")
      (description "YAGEO 0603 0 ohm")
      (fields
        (field (name "MOUSER PART NUMBER") "603-RC0603JR-070RL")
        (field (name "MANUFACTURER_PART_NUMBER") "RC0603JR-070RL")
      )
      (libsource (lib "Resistors") (part "RC0603JR-070RL"))
    )
    (comp (ref "R180")
      (value "0R")
      (footprint "0603")
      (description "YAGEO 0603 0 ohm")
      (fields
        (field (name "MOUSER PART NUMBER") "603-RC0603JR-070RL")
        (field (name "MANUFACTURER_PART_NUMBER") "RC0603JR-070RL")
      )
      (libsource (lib "Resistors") (part "RC0603JR-070RL"))
    )
    (comp (ref "R181")
      (value "0R")
      (footprint "0603")
      (description "YAGEO 0603 0 ohm")
      (fields
        (field (name "MOUSER PART NUMBER") "603-RC0603JR-070RL")
        (field (name "MANUFACTURER_PART_NUMBER") "RC0603JR-070RL")
      )
      (libsource (lib "Resistors") (part "RC0603JR-070RL"))
    )
    (comp (ref "R182")
      (value "0R")
      (footprint "0603")
      (description "YAGEO 0603 0 ohm")
      (fields
        (field (name "MOUSER PART NUMBER") "603-RC0603JR-070RL")
        (field (name "MANUFACTURER_PART_NUMBER") "RC0603JR-070RL")
      )
      (libsource (lib "Resistors") (part "RC0603JR-070RL"))
    )
    (comp (ref "R183")
      (value "0R")
      (footprint "0603")
      (description "YAGEO 0603 0 ohm")
      (fields
        (field (name "MOUSER PART NUMBER") "603-RC0603JR-070RL")
        (field (name "MANUFACTURER_PART_NUMBER") "RC0603JR-070RL")
      )
      (libsource (lib "Resistors") (part "RC0603JR-070RL"))
    )
    (comp (ref "R184")
      (value "0R")
      (footprint "0603")
      (description "YAGEO 0603 0 ohm")
      (fields
        (field (name "MOUSER PART NUMBER") "603-RC0603JR-070RL")
        (field (name "MANUFACTURER_PART_NUMBER") "RC0603JR-070RL")
      )
      (libsource (lib "Resistors") (part "RC0603JR-070RL"))
    )
    (comp (ref "R185")
      (value "0R")
      (footprint "0603")
      (description "YAGEO 0603 0 ohm")
      (fields
        (field (name "MOUSER PART NUMBER") "603-RC0603JR-070RL")
        (field (name "MANUFACTURER_PART_NUMBER") "RC0603JR-070RL")
      )
      (libsource (lib "Resistors") (part "RC0603JR-070RL"))
    )
    (comp (ref "R186")
      (value "0R")
      (footprint "0603")
      (description "YAGEO 0603 0 ohm")
      (fields
        (field (name "MOUSER PART NUMBER") "603-RC0603JR-070RL")
        (field (name "MANUFACTURER_PART_NUMBER") "RC0603JR-070RL")
      )
      (libsource (lib "Resistors") (part "RC0603JR-070RL"))
    )
    (comp (ref "R187")
      (value "0R")
      (footprint "0603")
      (description "YAGEO 0603 0 ohm")
      (fields
        (field (name "MOUSER PART NUMBER") "603-RC0603JR-070RL")
        (field (name "MANUFACTURER_PART_NUMBER") "RC0603JR-070RL")
      )
      (libsource (lib "Resistors") (part "RC0603JR-070RL"))
    )
    (comp (ref "R188")
      (value "0R")
      (footprint "0603")
      (description "YAGEO 0603 0 ohm")
      (fields
        (field (name "MOUSER PART NUMBER") "603-RC0603JR-070RL")
        (field (name "MANUFACTURER_PART_NUMBER") "RC0603JR-070RL")
      )
      (libsource (lib "Resistors") (part "RC0603JR-070RL"))
    )
    (comp (ref "R189")
      (value "0R")
      (footprint "0603")
      (description "YAGEO 0603 0 ohm")
      (fields
        (field (name "MOUSER PART NUMBER") "603-RC0603JR-070RL")
        (field (name "MANUFACTURER_PART_NUMBER") "RC0603JR-070RL")
      )
      (libsource (lib "Resistors") (part "RC0603JR-070RL"))
    )
    (comp (ref "R190")
      (value "0R")
      (footprint "0603")
      (description "YAGEO 0603 0 ohm")
      (fields
        (field (name "MOUSER PART NUMBER") "603-RC0603JR-070RL")
        (field (name "MANUFACTURER_PART_NUMBER") "RC0603JR-070RL")
      )
      (libsource (lib "Resistors") (part "RC0603JR-070RL"))
    )
    (comp (ref "R191")
      (value "0R")
      (footprint "0603")
      (description "YAGEO 0603 0 ohm")
      (fields
        (field (name "MOUSER PART NUMBER") "603-RC0603JR-070RL")
        (field (name "MANUFACTURER_PART_NUMBER") "RC0603JR-070RL")
      )
      (libsource (lib "Resistors") (part "RC0603JR-070RL"))
    )
    (comp (ref "R192")
      (value "0R")
      (footprint "0603")
      (description "YAGEO 0603 0 ohm")
      (fields
        (field (name "MOUSER PART NUMBER") "603-RC0603JR-070RL")
        (field (name "MANUFACTURER_PART_NUMBER") "RC0603JR-070RL")
      )
      (libsource (lib "Resistors") (part "RC0603JR-070RL"))
    )
    (comp (ref "R193")
      (value "0R")
      (footprint "0603")
      (description "YAGEO 0603 0 ohm")
      (fields
        (field (name "MOUSER PART NUMBER") "603-RC0603JR-070RL")
        (field (name "MANUFACTURER_PART_NUMBER") "RC0603JR-070RL")
      )
      (libsource (lib "Resistors") (part "RC0603JR-070RL"))
    )
    (comp (ref "TitleBlock_2") (value "TitleBlock") (libsource (lib "Misc") (part "TitleBlock")))
    (comp (ref "TP13")
      (value "TP")
      (footprint "TP")
      (fields
        (field (name "MANUFACTURER") "Samtec")
        (field (name "MANUFACTURER PART NUMBER") "TST-105-01-G-D")
      )
      (libsource (lib "") (part "TP_1"))
    )
    (comp (ref "TP14")
      (value "TP")
      (footprint "TP")
      (fields
        (field (name "MANUFACTURER") "Samtec")
        (field (name "MANUFACTURER PART NUMBER") "TST-105-01-G-D")
      )
      (libsource (lib "") (part "TP_2"))
    )
    (comp (ref "TP15")
      (value "TP")
      (footprint "TP")
      (fields
        (field (name "MANUFACTURER") "Samtec")
        (field (name "MANUFACTURER PART NUMBER") "TST-105-01-G-D")
      )
      (libsource (lib "") (part "TP_2"))
    )
    (comp (ref "TP16")
      (value "TP")
      (footprint "TP")
      (fields
        (field (name "MANUFACTURER") "Samtec")
        (field (name "MANUFACTURER PART NUMBER") "TST-105-01-G-D")
      )
      (libsource (lib "") (part "TP_1"))
    )
    (comp (ref "TP17")
      (value "TP")
      (footprint "TP")
      (fields
        (field (name "MANUFACTURER") "Samtec")
        (field (name "MANUFACTURER PART NUMBER") "TST-105-01-G-D")
      )
      (libsource (lib "") (part "TP_2"))
    )
    (comp (ref "TP18")
      (value "TP")
      (footprint "TP")
      (fields
        (field (name "MANUFACTURER") "Samtec")
        (field (name "MANUFACTURER PART NUMBER") "TST-105-01-G-D")
      )
      (libsource (lib "Misc") (part "TP"))
    )
    (comp (ref "TP19")
      (value "TP")
      (footprint "TP")
      (fields
        (field (name "MANUFACTURER") "Samtec")
        (field (name "MANUFACTURER PART NUMBER") "TST-105-01-G-D")
      )
      (libsource (lib "") (part "TP_1"))
    )
    (comp (ref "TP20")
      (value "TP")
      (footprint "TP")
      (fields
        (field (name "MANUFACTURER") "Samtec")
        (field (name "MANUFACTURER PART NUMBER") "TST-105-01-G-D")
      )
      (libsource (lib "") (part "TP_2"))
    )
    (comp (ref "TP21")
      (value "TP")
      (footprint "TP")
      (fields
        (field (name "MANUFACTURER") "Samtec")
        (field (name "MANUFACTURER PART NUMBER") "TST-105-01-G-D")
      )
      (libsource (lib "") (part "TP_2"))
    )
    (comp (ref "TP22")
      (value "TP")
      (footprint "TP")
      (fields
        (field (name "MANUFACTURER") "Samtec")
        (field (name "MANUFACTURER PART NUMBER") "TST-105-01-G-D")
      )
      (libsource (lib "") (part "TP_1"))
    )
    (comp (ref "U3")
      (value "SN74ABT240ADBR")
      (footprint "SOP65P780X200-20N")
      (description "Octal Buffers/Drivers With 3-State Outputs")
      (fields (field (name "MOUSER PART NUMBER") "595-SN74ABT240ADBR"))
      (libsource (lib "Logic") (part "SN74ABT240ADBR"))
    )
    (comp (ref "U4")
      (value "SN74AC04PWR")
      (footprint "SOP65P640X120-14N")
      (description "Hex Inverters")
      (fields (field (name "MOUSER PART NUMBER") "595-SN74AC04PWR"))
      (libsource (lib "Logic") (part "SN74AC04PWR"))
    )
    (comp (ref "U5")
      (value "SN74AC04PWR")
      (footprint "SOP65P640X120-14N")
      (description "Hex Inverters")
      (fields (field (name "MOUSER PART NUMBER") "595-SN74AC04PWR"))
      (libsource (lib "Logic") (part "SN74AC04PWR"))
    )
    (comp (ref "U6")
      (value "SN74AC04PWR")
      (footprint "SOP65P640X120-14N")
      (description "Hex Inverters")
      (fields (field (name "MOUSER PART NUMBER") "595-SN74AC04PWR"))
      (libsource (lib "Logic") (part "SN74AC04PWR"))
    )
  )
  (nets
    (net (code "1") (name "+3.3") (class "Default")
      (node (ref "R145") (pin "2") (pinfunction "2_2") (pintype "passive"))
    )
    (net (code "2") (name "+5") (class "Default")
      (node (ref "R120") (pin "2") (pinfunction "2_2") (pintype "passive"))
      (node (ref "R121") (pin "2") (pinfunction "2_2") (pintype "passive"))
      (node (ref "R122") (pin "2") (pinfunction "2_2") (pintype "passive"))
      (node (ref "R123") (pin "2") (pinfunction "2_2") (pintype "passive"))
      (node (ref "R124") (pin "2") (pinfunction "2_2") (pintype "passive"))
      (node (ref "R125") (pin "2") (pinfunction "2_2") (pintype "passive"))
      (node (ref "R126") (pin "2") (pinfunction "2_2") (pintype "passive"))
      (node (ref "R127") (pin "2") (pinfunction "2_2") (pintype "passive"))
      (node (ref "R128") (pin "2") (pinfunction "2_2") (pintype "passive"))
      (node (ref "R129") (pin "2") (pinfunction "2_2") (pintype "passive"))
      (node (ref "R130") (pin "2") (pinfunction "2_2") (pintype "passive"))
      (node (ref "R131") (pin "2") (pinfunction "2_2") (pintype "passive"))
      (node (ref "R132") (pin "2") (pinfunction "2_2") (pintype "passive"))
      (node (ref "R133") (pin "2") (pinfunction "2_2") (pintype "passive"))
      (node (ref "R134") (pin "2") (pinfunction "2_2") (pintype "passive"))
      (node (ref "R135") (pin "2") (pinfunction "2_2") (pintype "passive"))
      (node (ref "R136") (pin "2") (pinfunction "2_2") (pintype "passive"))
      (node (ref "R137") (pin "2") (pinfunction "2_2") (pintype "passive"))
      (node (ref "R138") (pin "2") (pinfunction "2_2") (pintype "passive"))
      (node (ref "R139") (pin "2") (pinfunction "2_2") (pintype "passive"))
      (node (ref "R140") (pin "2") (pinfunction "2_2") (pintype "passive"))
      (node (ref "R141") (pin "2") (pinfunction "2_2") (pintype "passive"))
      (node (ref "R142") (pin "2") (pinfunction "2_2") (pintype "passive"))
      (node (ref "R143") (pin "2") (pinfunction "2_2") (pintype "passive"))
      (node (ref "R144") (pin "2") (pinfunction "2_2") (pintype "passive"))
      (node (ref "R150") (pin "2") (pinfunction "2_2") (pintype "passive"))
      (node (ref "R151") (pin "2") (pinfunction "2_2") (pintype "passive"))
      (node (ref "R152") (pin "2") (pinfunction "2_2") (pintype "passive"))
      (node (ref "R153") (pin "2") (pinfunction "2_2") (pintype "passive"))
      (node (ref "R154") (pin "2") (pinfunction "2_2") (pintype "passive"))
      (node (ref "R155") (pin "2") (pinfunction "2_2") (pintype "passive"))
      (node (ref "R156") (pin "2") (pinfunction "2_2") (pintype "passive"))
      (node (ref "R157") (pin "2") (pinfunction "2_2") (pintype "passive"))
      (node (ref "R169") (pin "2") (pinfunction "2_2") (pintype "passive"))
      (node (ref "R170") (pin "2") (pinfunction "2_2") (pintype "passive"))
      (node (ref "R171") (pin "2") (pinfunction "2_2") (pintype "passive"))
      (node (ref "R172") (pin "2") (pinfunction "2_2") (pintype "passive"))
      (node (ref "U3") (pin "20") (pinfunction "VCC_20") (pintype "passive"))
      (node (ref "U4") (pin "14") (pinfunction "VCC_14") (pintype "passive"))
      (node (ref "U5") (pin "14") (pinfunction "VCC_14") (pintype "passive"))
      (node (ref "U6") (pin "14") (pinfunction "VCC_14") (pintype "passive"))
    )
    (net (code "3") (name "/75ALS194EN") (class "Default")
      (node (ref "R191") (pin "2") (pinfunction "2_2") (pintype "passive"))
      (node (ref "TP15") (pin "1") (pinfunction "1_1") (pintype "passive"))
    )
    (net (code "4") (name "/75ALS194EN_INV") (class "Default")
      (node (ref "LED11") (pin "1") (pinfunction "K_1") (pintype "passive"))
      (node (ref "R190") (pin "1") (pinfunction "1_1") (pintype "passive"))
      (node (ref "TP18") (pin "1") (pinfunction "1_1") (pintype "passive"))
    )
    (net (code "5") (name "/CPU_CS") (class "Default")
      (node (ref "LED13") (pin "1") (pinfunction "K_1") (pintype "passive"))
    )
    (net (code "6") (name "/CPU_D0") (class "Default")
      (node (ref "U3") (pin "2") (pinfunction "1A1_2") (pintype "passive"))
    )
    (net (code "7") (name "/CPU_D1") (class "Default")
      (node (ref "U3") (pin "4") (pinfunction "1A2_4") (pintype "passive"))
    )
    (net (code "8") (name "/CPU_D2") (class "Default")
      (node (ref "U3") (pin "6") (pinfunction "1A3_6") (pintype "passive"))
    )
    (net (code "9") (name "/CPU_D3") (class "Default")
      (node (ref "U3") (pin "8") (pinfunction "1A4_8") (pintype "passive"))
    )
    (net (code "10") (name "/CPU_D4") (class "Default")
      (node (ref "U3") (pin "11") (pinfunction "2A1_11") (pintype "passive"))
    )
    (net (code "11") (name "/CPU_D5") (class "Default")
      (node (ref "U3") (pin "13") (pinfunction "2A2_13") (pintype "passive"))
    )
    (net (code "12") (name "/CPU_D6") (class "Default")
      (node (ref "U3") (pin "15") (pinfunction "2A3_15") (pintype "passive"))
    )
    (net (code "13") (name "/CPU_D7") (class "Default")
      (node (ref "U3") (pin "17") (pinfunction "2A4_17") (pintype "passive"))
    )
    (net (code "14") (name "/CPU_Reset") (class "Default")
      (node (ref "LED12") (pin "1") (pinfunction "K_1") (pintype "passive"))
    )
    (net (code "15") (name "/CPU_RnW") (class "Default")
      (node (ref "LED16") (pin "1") (pinfunction "K_1") (pintype "passive"))
      (node (ref "R193") (pin "2") (pinfunction "2_2") (pintype "passive"))
    )
    (net (code "16") (name "/CPU_RnW_Inverted") (class "Default")
      (node (ref "LED15") (pin "1") (pinfunction "K_1") (pintype "passive"))
      (node (ref "R192") (pin "1") (pinfunction "1_1") (pintype "passive"))
    )
    (net (code "17") (name "/CPU_nInt") (class "Default")
      (node (ref "LED14") (pin "1") (pinfunction "K_1") (pintype "passive"))
    )
    (net (code "18") (name "/Digital_Output_0") (class "Default")
      (node (ref "R147") (pin "2") (pinfunction "2_2") (pintype "passive"))
    )
    (net (code "19") (name "/Digital_Output_1") (class "Default")
      (node (ref "R149") (pin "2") (pinfunction "2_2") (pintype "passive"))
    )
    (net (code "20") (name "/Digital_Output_2") (class "Default")
      (node (ref "R159") (pin "2") (pinfunction "2_2") (pintype "passive"))
    )
    (net (code "21") (name "/Digital_Output_3") (class "Default")
      (node (ref "R161") (pin "2") (pinfunction "2_2") (pintype "passive"))
    )
    (net (code "22") (name "/Digital_Output_4") (class "Default")
      (node (ref "R163") (pin "2") (pinfunction "2_2") (pintype "passive"))
    )
    (net (code "23") (name "/Digital_Output_5") (class "Default")
      (node (ref "R165") (pin "2") (pinfunction "2_2") (pintype "passive"))
    )
    (net (code "24") (name "/Digital_Output_6") (class "Default")
      (node (ref "R181") (pin "2") (pinfunction "2_2") (pintype "passive"))
    )
    (net (code "25") (name "/Digital_Output_6_Inv") (class "Default")
      (node (ref "LED18") (pin "1") (pinfunction "K_1") (pintype "passive"))
      (node (ref "R180") (pin "1") (pinfunction "1_1") (pintype "passive"))
    )
    (net (code "26") (name "/Digital_Output_7") (class "Default")
      (node (ref "R185") (pin "2") (pinfunction "2_2") (pintype "passive"))
    )
    (net (code "27") (name "/Digital_Output_7_Inv") (class "Default")
      (node (ref "LED17") (pin "1") (pinfunction "K_1") (pintype "passive"))
      (node (ref "R184") (pin "1") (pinfunction "1_1") (pintype "passive"))
    )
    (net (code "28") (name "/Digital_Output_Source_0") (class "Default")
      (node (ref "R166") (pin "2") (pinfunction "2_2") (pintype "passive"))
    )
    (net (code "29") (name "/Digital_Output_Source_1") (class "Default")
      (node (ref "R167") (pin "2") (pinfunction "2_2") (pintype "passive"))
    )
    (net (code "30") (name "/Digital_Output_Source_2") (class "Default")
      (node (ref "R168") (pin "2") (pinfunction "2_2") (pintype "passive"))
    )
    (net (code "31") (name "/Digital_Output_Source_3") (class "Default")
      (node (ref "R173") (pin "2") (pinfunction "2_2") (pintype "passive"))
    )
    (net (code "32") (name "/Digital_Output_Source_4") (class "Default")
      (node (ref "R174") (pin "2") (pinfunction "2_2") (pintype "passive"))
    )
    (net (code "33") (name "/Digital_Output_Source_5") (class "Default")
      (node (ref "R175") (pin "2") (pinfunction "2_2") (pintype "passive"))
    )
    (net (code "34") (name "/Digital_Output_Source_6") (class "Default")
      (node (ref "R176") (pin "2") (pinfunction "2_2") (pintype "passive"))
    )
    (net (code "35") (name "/Digital_Output_Source_7") (class "Default")
      (node (ref "R177") (pin "2") (pinfunction "2_2") (pintype "passive"))
    )
    (net (code "36") (name "/RCLK") (class "Default")
      (node (ref "R183") (pin "2") (pinfunction "2_2") (pintype "passive"))
    )
    (net (code "37") (name "/SRCLK") (class "Default")
      (node (ref "R179") (pin "2") (pinfunction "2_2") (pintype "passive"))
    )
    (net (code "38") (name "/SR_CLR") (class "Default")
      (node (ref "LED10") (pin "1") (pinfunction "K_1") (pintype "passive"))
    )
    (net (code "39") (name "/SR_OE") (class "Default")
      (node (ref "LED9") (pin "1") (pinfunction "K_1") (pintype "passive"))
    )
    (net (code "40") (name "/Ser_Data_0") (class "Default")
      (node (ref "R187") (pin "2") (pinfunction "2_2") (pintype "passive"))
    )
    (net (code "41") (name "/Ser_Data_1") (class "Default")
      (node (ref "R189") (pin "2") (pinfunction "2_2") (pintype "passive"))
    )
    (net (code "42") (name "GND") (class "Default")
      (node (ref "LED25") (pin "1") (pinfunction "K_1") (pintype "passive"))
      (node (ref "LED26") (pin "1") (pinfunction "K_1") (pintype "passive"))
      (node (ref "U3") (pin "1") (pinfunction "~{1}OE_1") (pintype "passive"))
      (node (ref "U3") (pin "10") (pinfunction "GND_10") (pintype "passive"))
      (node (ref "U3") (pin "19") (pinfunction "~{2}OE_19") (pintype "passive"))
      (node (ref "U4") (pin "7") (pinfunction "GND_7") (pintype "passive"))
      (node (ref "U5") (pin "7") (pinfunction "GND_7") (pintype "passive"))
      (node (ref "U6") (pin "7") (pinfunction "GND_7") (pintype "passive"))
    )
    (net (code "43") (name "Net-(LED1-A)") (class "Default")
      (node (ref "LED1") (pin "2") (pinfunction "A_2") (pintype "passive"))
      (node (ref "R120") (pin "1") (pinfunction "1_1") (pintype "passive"))
    )
    (net (code "44") (name "Net-(LED1-K)") (class "Default")
      (node (ref "LED1") (pin "1") (pinfunction "K_1") (pintype "passive"))
      (node (ref "U3") (pin "18") (pinfunction "1Y1_18") (pintype "passive"))
    )
    (net (code "45") (name "Net-(LED2-A)") (class "Default")
      (node (ref "LED2") (pin "2") (pinfunction "A_2") (pintype "passive"))
      (node (ref "R121") (pin "1") (pinfunction "1_1") (pintype "passive"))
    )
    (net (code "46") (name "Net-(LED2-K)") (class "Default")
      (node (ref "LED2") (pin "1") (pinfunction "K_1") (pintype "passive"))
      (node (ref "U3") (pin "16") (pinfunction "1Y2_16") (pintype "passive"))
    )
    (net (code "47") (name "Net-(LED3-A)") (class "Default")
      (node (ref "LED3") (pin "2") (pinfunction "A_2") (pintype "passive"))
      (node (ref "R122") (pin "1") (pinfunction "1_1") (pintype "passive"))
    )
    (net (code "48") (name "Net-(LED3-K)") (class "Default")
      (node (ref "LED3") (pin "1") (pinfunction "K_1") (pintype "passive"))
      (node (ref "U3") (pin "14") (pinfunction "1Y3_14") (pintype "passive"))
    )
    (net (code "49") (name "Net-(LED4-A)") (class "Default")
      (node (ref "LED4") (pin "2") (pinfunction "A_2") (pintype "passive"))
      (node (ref "R123") (pin "1") (pinfunction "1_1") (pintype "passive"))
    )
    (net (code "50") (name "Net-(LED4-K)") (class "Default")
      (node (ref "LED4") (pin "1") (pinfunction "K_1") (pintype "passive"))
      (node (ref "U3") (pin "12") (pinfunction "1Y4_12") (pintype "passive"))
    )
    (net (code "51") (name "Net-(LED5-A)") (class "Default")
      (node (ref "LED5") (pin "2") (pinfunction "A_2") (pintype "passive"))
      (node (ref "R124") (pin "1") (pinfunction "1_1") (pintype "passive"))
    )
    (net (code "52") (name "Net-(LED5-K)") (class "Default")
      (node (ref "LED5") (pin "1") (pinfunction "K_1") (pintype "passive"))
      (node (ref "U3") (pin "9") (pinfunction "2Y1_9") (pintype "passive"))
    )
    (net (code "53") (name "Net-(LED6-A)") (class "Default")
      (node (ref "LED6") (pin "2") (pinfunction "A_2") (pintype "passive"))
      (node (ref "R125") (pin "1") (pinfunction "1_1") (pintype "passive"))
    )
    (net (code "54") (name "Net-(LED6-K)") (class "Default")
      (node (ref "LED6") (pin "1") (pinfunction "K_1") (pintype "passive"))
      (node (ref "U3") (pin "7") (pinfunction "2Y2_7") (pintype "passive"))
    )
    (net (code "55") (name "Net-(LED7-A)") (class "Default")
      (node (ref "LED7") (pin "2") (pinfunction "A_2") (pintype "passive"))
      (node (ref "R126") (pin "1") (pinfunction "1_1") (pintype "passive"))
    )
    (net (code "56") (name "Net-(LED7-K)") (class "Default")
      (node (ref "LED7") (pin "1") (pinfunction "K_1") (pintype "passive"))
      (node (ref "U3") (pin "5") (pinfunction "2Y3_5") (pintype "passive"))
    )
    (net (code "57") (name "Net-(LED8-A)") (class "Default")
      (node (ref "LED8") (pin "2") (pinfunction "A_2") (pintype "passive"))
      (node (ref "R127") (pin "1") (pinfunction "1_1") (pintype "passive"))
    )
    (net (code "58") (name "Net-(LED8-K)") (class "Default")
      (node (ref "LED8") (pin "1") (pinfunction "K_1") (pintype "passive"))
      (node (ref "U3") (pin "3") (pinfunction "2Y4_3") (pintype "passive"))
    )
    (net (code "59") (name "Net-(LED9-A)") (class "Default")
      (node (ref "LED9") (pin "2") (pinfunction "A_2") (pintype "passive"))
      (node (ref "R128") (pin "1") (pinfunction "1_1") (pintype "passive"))
    )
    (net (code "60") (name "Net-(LED10-A)") (class "Default")
      (node (ref "LED10") (pin "2") (pinfunction "A_2") (pintype "passive"))
      (node (ref "R129") (pin "1") (pinfunction "1_1") (pintype "passive"))
    )
    (net (code "61") (name "Net-(LED11-A)") (class "Default")
      (node (ref "LED11") (pin "2") (pinfunction "A_2") (pintype "passive"))
      (node (ref "R130") (pin "1") (pinfunction "1_1") (pintype "passive"))
    )
    (net (code "62") (name "Net-(LED12-A)") (class "Default")
      (node (ref "LED12") (pin "2") (pinfunction "A_2") (pintype "passive"))
      (node (ref "R131") (pin "1") (pinfunction "1_1") (pintype "passive"))
    )
    (net (code "63") (name "Net-(LED13-A)") (class "Default")
      (node (ref "LED13") (pin "2") (pinfunction "A_2") (pintype "passive"))
      (node (ref "R132") (pin "1") (pinfunction "1_1") (pintype "passive"))
    )
    (net (code "64") (name "Net-(LED14-A)") (class "Default")
      (node (ref "LED14") (pin "2") (pinfunction "A_2") (pintype "passive"))
      (node (ref "R133") (pin "1") (pinfunction "1_1") (pintype "passive"))
    )
    (net (code "65") (name "Net-(LED15-A)") (class "Default")
      (node (ref "LED15") (pin "2") (pinfunction "A_2") (pintype "passive"))
      (node (ref "R134") (pin "1") (pinfunction "1_1") (pintype "passive"))
    )
    (net (code "66") (name "Net-(LED16-A)") (class "Default")
      (node (ref "LED16") (pin "2") (pinfunction "A_2") (pintype "passive"))
      (node (ref "R135") (pin "1") (pinfunction "1_1") (pintype "passive"))
    )
    (net (code "67") (name "Net-(LED17-A)") (class "Default")
      (node (ref "LED17") (pin "2") (pinfunction "A_2") (pintype "passive"))
      (node (ref "R136") (pin "1") (pinfunction "1_1") (pintype "passive"))
    )
    (net (code "68") (name "Net-(LED18-A)") (class "Default")
      (node (ref "LED18") (pin "2") (pinfunction "A_2") (pintype "passive"))
      (node (ref "R137") (pin "1") (pinfunction "1_1") (pintype "passive"))
    )
    (net (code "69") (name "Net-(LED19-A)") (class "Default")
      (node (ref "LED19") (pin "2") (pinfunction "A_2") (pintype "passive"))
      (node (ref "R138") (pin "1") (pinfunction "1_1") (pintype "passive"))
    )
    (net (code "70") (name "Net-(LED19-K)") (class "Default")
      (node (ref "LED19") (pin "1") (pinfunction "K_1") (pintype "passive"))
      (node (ref "R164") (pin "1") (pinfunction "1_1") (pintype "passive"))
    )
    (net (code "71") (name "Net-(LED20-A)") (class "Default")
      (node (ref "LED20") (pin "2") (pinfunction "A_2") (pintype "passive"))
      (node (ref "R139") (pin "1") (pinfunction "1_1") (pintype "passive"))
    )
    (net (code "72") (name "Net-(LED20-K)") (class "Default")
      (node (ref "LED20") (pin "1") (pinfunction "K_1") (pintype "passive"))
      (node (ref "R162") (pin "1") (pinfunction "1_1") (pintype "passive"))
    )
    (net (code "73") (name "Net-(LED21-A)") (class "Default")
      (node (ref "LED21") (pin "2") (pinfunction "A_2") (pintype "passive"))
      (node (ref "R140") (pin "1") (pinfunction "1_1") (pintype "passive"))
    )
    (net (code "74") (name "Net-(LED21-K)") (class "Default")
      (node (ref "LED21") (pin "1") (pinfunction "K_1") (pintype "passive"))
      (node (ref "R160") (pin "1") (pinfunction "1_1") (pintype "passive"))
    )
    (net (code "75") (name "Net-(LED22-A)") (class "Default")
      (node (ref "LED22") (pin "2") (pinfunction "A_2") (pintype "passive"))
      (node (ref "R141") (pin "1") (pinfunction "1_1") (pintype "passive"))
    )
    (net (code "76") (name "Net-(LED22-K)") (class "Default")
      (node (ref "LED22") (pin "1") (pinfunction "K_1") (pintype "passive"))
      (node (ref "R158") (pin "1") (pinfunction "1_1") (pintype "passive"))
    )
    (net (code "77") (name "Net-(LED23-A)") (class "Default")
      (node (ref "LED23") (pin "2") (pinfunction "A_2") (pintype "passive"))
      (node (ref "R142") (pin "1") (pinfunction "1_1") (pintype "passive"))
    )
    (net (code "78") (name "Net-(LED23-K)") (class "Default")
      (node (ref "LED23") (pin "1") (pinfunction "K_1") (pintype "passive"))
      (node (ref "R148") (pin "1") (pinfunction "1_1") (pintype "passive"))
    )
    (net (code "79") (name "Net-(LED24-A)") (class "Default")
      (node (ref "LED24") (pin "2") (pinfunction "A_2") (pintype "passive"))
      (node (ref "R143") (pin "1") (pinfunction "1_1") (pintype "passive"))
    )
    (net (code "80") (name "Net-(LED24-K)") (class "Default")
      (node (ref "LED24") (pin "1") (pinfunction "K_1") (pintype "passive"))
      (node (ref "R146") (pin "1") (pinfunction "1_1") (pintype "passive"))
    )
    (net (code "81") (name "Net-(LED25-A)") (class "Default")
      (node (ref "LED25") (pin "2") (pinfunction "A_2") (pintype "passive"))
      (node (ref "R144") (pin "1") (pinfunction "1_1") (pintype "passive"))
    )
    (net (code "82") (name "Net-(LED26-A)") (class "Default")
      (node (ref "LED26") (pin "2") (pinfunction "A_2") (pintype "passive"))
      (node (ref "R145") (pin "1") (pinfunction "1_1") (pintype "passive"))
    )
    (net (code "83") (name "Net-(LED27-A)") (class "Default")
      (node (ref "LED27") (pin "2") (pinfunction "A_2") (pintype "passive"))
      (node (ref "R150") (pin "1") (pinfunction "1_1") (pintype "passive"))
    )
    (net (code "84") (name "Net-(LED27-K)") (class "Default")
      (node (ref "LED27") (pin "1") (pinfunction "K_1") (pintype "passive"))
      (node (ref "R177") (pin "1") (pinfunction "1_1") (pintype "passive"))
    )
    (net (code "85") (name "Net-(LED28-A)") (class "Default")
      (node (ref "LED28") (pin "2") (pinfunction "A_2") (pintype "passive"))
      (node (ref "R151") (pin "1") (pinfunction "1_1") (pintype "passive"))
    )
    (net (code "86") (name "Net-(LED28-K)") (class "Default")
      (node (ref "LED28") (pin "1") (pinfunction "K_1") (pintype "passive"))
      (node (ref "R176") (pin "1") (pinfunction "1_1") (pintype "passive"))
    )
    (net (code "87") (name "Net-(LED29-A)") (class "Default")
      (node (ref "LED29") (pin "2") (pinfunction "A_2") (pintype "passive"))
      (node (ref "R152") (pin "1") (pinfunction "1_1") (pintype "passive"))
    )
    (net (code "88") (name "Net-(LED29-K)") (class "Default")
      (node (ref "LED29") (pin "1") (pinfunction "K_1") (pintype "passive"))
      (node (ref "R175") (pin "1") (pinfunction "1_1") (pintype "passive"))
    )
    (net (code "89") (name "Net-(LED30-A)") (class "Default")
      (node (ref "LED30") (pin "2") (pinfunction "A_2") (pintype "passive"))
      (node (ref "R153") (pin "1") (pinfunction "1_1") (pintype "passive"))
    )
    (net (code "90") (name "Net-(LED30-K)") (class "Default")
      (node (ref "LED30") (pin "1") (pinfunction "K_1") (pintype "passive"))
      (node (ref "R174") (pin "1") (pinfunction "1_1") (pintype "passive"))
    )
    (net (code "91") (name "Net-(LED31-A)") (class "Default")
      (node (ref "LED31") (pin "2") (pinfunction "A_2") (pintype "passive"))
      (node (ref "R154") (pin "1") (pinfunction "1_1") (pintype "passive"))
    )
    (net (code "92") (name "Net-(LED31-K)") (class "Default")
      (node (ref "LED31") (pin "1") (pinfunction "K_1") (pintype "passive"))
      (node (ref "R173") (pin "1") (pinfunction "1_1") (pintype "passive"))
    )
    (net (code "93") (name "Net-(LED32-A)") (class "Default")
      (node (ref "LED32") (pin "2") (pinfunction "A_2") (pintype "passive"))
      (node (ref "R155") (pin "1") (pinfunction "1_1") (pintype "passive"))
    )
    (net (code "94") (name "Net-(LED32-K)") (class "Default")
      (node (ref "LED32") (pin "1") (pinfunction "K_1") (pintype "passive"))
      (node (ref "R168") (pin "1") (pinfunction "1_1") (pintype "passive"))
    )
    (net (code "95") (name "Net-(LED33-A)") (class "Default")
      (node (ref "LED33") (pin "2") (pinfunction "A_2") (pintype "passive"))
      (node (ref "R156") (pin "1") (pinfunction "1_1") (pintype "passive"))
    )
    (net (code "96") (name "Net-(LED33-K)") (class "Default")
      (node (ref "LED33") (pin "1") (pinfunction "K_1") (pintype "passive"))
      (node (ref "R167") (pin "1") (pinfunction "1_1") (pintype "passive"))
    )
    (net (code "97") (name "Net-(LED34-A)") (class "Default")
      (node (ref "LED34") (pin "2") (pinfunction "A_2") (pintype "passive"))
      (node (ref "R157") (pin "1") (pinfunction "1_1") (pintype "passive"))
    )
    (net (code "98") (name "Net-(LED34-K)") (class "Default")
      (node (ref "LED34") (pin "1") (pinfunction "K_1") (pintype "passive"))
      (node (ref "R166") (pin "1") (pinfunction "1_1") (pintype "passive"))
    )
    (net (code "99") (name "Net-(LED35-A)") (class "Default")
      (node (ref "LED35") (pin "2") (pinfunction "A_2") (pintype "passive"))
      (node (ref "R169") (pin "1") (pinfunction "1_1") (pintype "passive"))
    )
    (net (code "100") (name "Net-(LED35-K)") (class "Default")
      (node (ref "LED35") (pin "1") (pinfunction "K_1") (pintype "passive"))
      (node (ref "R188") (pin "1") (pinfunction "1_1") (pintype "passive"))
    )
    (net (code "101") (name "Net-(LED36-A)") (class "Default")
      (node (ref "LED36") (pin "2") (pinfunction "A_2") (pintype "passive"))
      (node (ref "R170") (pin "1") (pinfunction "1_1") (pintype "passive"))
    )
    (net (code "102") (name "Net-(LED36-K)") (class "Default")
      (node (ref "LED36") (pin "1") (pinfunction "K_1") (pintype "passive"))
      (node (ref "R186") (pin "1") (pinfunction "1_1") (pintype "passive"))
    )
    (net (code "103") (name "Net-(LED37-A)") (class "Default")
      (node (ref "LED37") (pin "2") (pinfunction "A_2") (pintype "passive"))
      (node (ref "R171") (pin "1") (pinfunction "1_1") (pintype "passive"))
    )
    (net (code "104") (name "Net-(LED37-K)") (class "Default")
      (node (ref "LED37") (pin "1") (pinfunction "K_1") (pintype "passive"))
      (node (ref "R182") (pin "1") (pinfunction "1_1") (pintype "passive"))
    )
    (net (code "105") (name "Net-(LED38-A)") (class "Default")
      (node (ref "LED38") (pin "2") (pinfunction "A_2") (pintype "passive"))
      (node (ref "R172") (pin "1") (pinfunction "1_1") (pintype "passive"))
    )
    (net (code "106") (name "Net-(LED38-K)") (class "Default")
      (node (ref "LED38") (pin "1") (pinfunction "K_1") (pintype "passive"))
      (node (ref "R178") (pin "1") (pinfunction "1_1") (pintype "passive"))
    )
    (net (code "107") (name "Net-(U4-1A)") (class "Default")
      (node (ref "R147") (pin "1") (pinfunction "1_1") (pintype "passive"))
      (node (ref "U4") (pin "1") (pinfunction "1A_1") (pintype "passive"))
    )
    (net (code "108") (name "Net-(U4-1Y)") (class "Default")
      (node (ref "R146") (pin "2") (pinfunction "2_2") (pintype "passive"))
      (node (ref "U4") (pin "2") (pinfunction "1Y_2") (pintype "passive"))
    )
    (net (code "109") (name "Net-(U4-2A)") (class "Default")
      (node (ref "R149") (pin "1") (pinfunction "1_1") (pintype "passive"))
      (node (ref "U4") (pin "3") (pinfunction "2A_3") (pintype "passive"))
    )
    (net (code "110") (name "Net-(U4-2Y)") (class "Default")
      (node (ref "R148") (pin "2") (pinfunction "2_2") (pintype "passive"))
      (node (ref "U4") (pin "4") (pinfunction "2Y_4") (pintype "passive"))
    )
    (net (code "111") (name "Net-(U4-3A)") (class "Default")
      (node (ref "R159") (pin "1") (pinfunction "1_1") (pintype "passive"))
      (node (ref "U4") (pin "5") (pinfunction "3A_5") (pintype "passive"))
    )
    (net (code "112") (name "Net-(U4-3Y)") (class "Default")
      (node (ref "R158") (pin "2") (pinfunction "2_2") (pintype "passive"))
      (node (ref "U4") (pin "6") (pinfunction "3Y_6") (pintype "passive"))
    )
    (net (code "113") (name "Net-(U4-4A)") (class "Default")
      (node (ref "R161") (pin "1") (pinfunction "1_1") (pintype "passive"))
      (node (ref "U4") (pin "9") (pinfunction "4A_9") (pintype "passive"))
    )
    (net (code "114") (name "Net-(U4-4Y)") (class "Default")
      (node (ref "R160") (pin "2") (pinfunction "2_2") (pintype "passive"))
      (node (ref "U4") (pin "8") (pinfunction "4Y_8") (pintype "passive"))
    )
    (net (code "115") (name "Net-(U4-5A)") (class "Default")
      (node (ref "R163") (pin "1") (pinfunction "1_1") (pintype "passive"))
      (node (ref "U4") (pin "11") (pinfunction "5A_11") (pintype "passive"))
    )
    (net (code "116") (name "Net-(U4-5Y)") (class "Default")
      (node (ref "R162") (pin "2") (pinfunction "2_2") (pintype "passive"))
      (node (ref "U4") (pin "10") (pinfunction "5Y_10") (pintype "passive"))
    )
    (net (code "117") (name "Net-(U4-6A)") (class "Default")
      (node (ref "R165") (pin "1") (pinfunction "1_1") (pintype "passive"))
      (node (ref "U4") (pin "13") (pinfunction "6A_13") (pintype "passive"))
    )
    (net (code "118") (name "Net-(U4-6Y)") (class "Default")
      (node (ref "R164") (pin "2") (pinfunction "2_2") (pintype "passive"))
      (node (ref "U4") (pin "12") (pinfunction "6Y_12") (pintype "passive"))
    )
    (net (code "119") (name "Net-(U5-1A)") (class "Default")
      (node (ref "R179") (pin "1") (pinfunction "1_1") (pintype "passive"))
      (node (ref "U5") (pin "1") (pinfunction "1A_1") (pintype "passive"))
    )
    (net (code "120") (name "Net-(U5-1Y)") (class "Default")
      (node (ref "R178") (pin "2") (pinfunction "2_2") (pintype "passive"))
      (node (ref "U5") (pin "2") (pinfunction "1Y_2") (pintype "passive"))
    )
    (net (code "121") (name "Net-(U5-2A)") (class "Default")
      (node (ref "R183") (pin "1") (pinfunction "1_1") (pintype "passive"))
      (node (ref "U5") (pin "3") (pinfunction "2A_3") (pintype "passive"))
    )
    (net (code "122") (name "Net-(U5-2Y)") (class "Default")
      (node (ref "R182") (pin "2") (pinfunction "2_2") (pintype "passive"))
      (node (ref "U5") (pin "4") (pinfunction "2Y_4") (pintype "passive"))
    )
    (net (code "123") (name "Net-(U5-3A)") (class "Default")
      (node (ref "R187") (pin "1") (pinfunction "1_1") (pintype "passive"))
      (node (ref "U5") (pin "5") (pinfunction "3A_5") (pintype "passive"))
    )
    (net (code "124") (name "Net-(U5-3Y)") (class "Default")
      (node (ref "R186") (pin "2") (pinfunction "2_2") (pintype "passive"))
      (node (ref "U5") (pin "6") (pinfunction "3Y_6") (pintype "passive"))
    )
    (net (code "125") (name "Net-(U5-4A)") (class "Default")
      (node (ref "R189") (pin "1") (pinfunction "1_1") (pintype "passive"))
      (node (ref "U5") (pin "9") (pinfunction "4A_9") (pintype "passive"))
    )
    (net (code "126") (name "Net-(U5-4Y)") (class "Default")
      (node (ref "R188") (pin "2") (pinfunction "2_2") (pintype "passive"))
      (node (ref "U5") (pin "8") (pinfunction "4Y_8") (pintype "passive"))
    )
    (net (code "127") (name "Net-(U5-5A)") (class "Default")
      (node (ref "R191") (pin "1") (pinfunction "1_1") (pintype "passive"))
      (node (ref "U5") (pin "11") (pinfunction "5A_11") (pintype "passive"))
    )
    (net (code "128") (name "Net-(U5-5Y)") (class "Default")
      (node (ref "R190") (pin "2") (pinfunction "2_2") (pintype "passive"))
      (node (ref "U5") (pin "10") (pinfunction "5Y_10") (pintype "passive"))
    )
    (net (code "129") (name "Net-(U5-6A)") (class "Default")
      (node (ref "R193") (pin "1") (pinfunction "1_1") (pintype "passive"))
      (node (ref "U5") (pin "13") (pinfunction "6A_13") (pintype "passive"))
    )
    (net (code "130") (name "Net-(U5-6Y)") (class "Default")
      (node (ref "R192") (pin "2") (pinfunction "2_2") (pintype "passive"))
      (node (ref "U5") (pin "12") (pinfunction "6Y_12") (pintype "passive"))
    )
    (net (code "131") (name "Net-(U6-1A)") (class "Default")
      (node (ref "R181") (pin "1") (pinfunction "1_1") (pintype "passive"))
      (node (ref "U6") (pin "1") (pinfunction "1A_1") (pintype "passive"))
    )
    (net (code "132") (name "Net-(U6-1Y)") (class "Default")
      (node (ref "R180") (pin "2") (pinfunction "2_2") (pintype "passive"))
      (node (ref "U6") (pin "2") (pinfunction "1Y_2") (pintype "passive"))
    )
    (net (code "133") (name "Net-(U6-2A)") (class "Default")
      (node (ref "R185") (pin "1") (pinfunction "1_1") (pintype "passive"))
      (node (ref "U6") (pin "3") (pinfunction "2A_3") (pintype "passive"))
    )
    (net (code "134") (name "Net-(U6-2Y)") (class "Default")
      (node (ref "R184") (pin "2") (pinfunction "2_2") (pintype "passive"))
      (node (ref "U6") (pin "4") (pinfunction "2Y_4") (pintype "passive"))
    )
    (net (code "135") (name "Net-(U6-3A)") (class "Default")
      (node (ref "TP14") (pin "1") (pinfunction "1_1") (pintype "passive"))
      (node (ref "U6") (pin "5") (pinfunction "3A_5") (pintype "passive"))
    )
    (net (code "136") (name "Net-(U6-3Y)") (class "Default")
      (node (ref "TP13") (pin "1") (pinfunction "1_1") (pintype "passive"))
      (node (ref "U6") (pin "6") (pinfunction "3Y_6") (pintype "passive"))
    )
    (net (code "137") (name "Net-(U6-4A)") (class "Default")
      (node (ref "TP17") (pin "1") (pinfunction "1_1") (pintype "passive"))
      (node (ref "U6") (pin "9") (pinfunction "4A_9") (pintype "passive"))
    )
    (net (code "138") (name "Net-(U6-4Y)") (class "Default")
      (node (ref "TP16") (pin "1") (pinfunction "1_1") (pintype "passive"))
      (node (ref "U6") (pin "8") (pinfunction "4Y_8") (pintype "passive"))
    )
    (net (code "139") (name "Net-(U6-5A)") (class "Default")
      (node (ref "TP20") (pin "1") (pinfunction "1_1") (pintype "passive"))
      (node (ref "U6") (pin "11") (pinfunction "5A_11") (pintype "passive"))
    )
    (net (code "140") (name "Net-(U6-5Y)") (class "Default")
      (node (ref "TP19") (pin "1") (pinfunction "1_1") (pintype "passive"))
      (node (ref "U6") (pin "10") (pinfunction "5Y_10") (pintype "passive"))
    )
    (net (code "141") (name "Net-(U6-6A)") (class "Default")
      (node (ref "TP21") (pin "1") (pinfunction "1_1") (pintype "passive"))
      (node (ref "U6") (pin "13") (pinfunction "6A_13") (pintype "passive"))
    )
    (net (code "142") (name "Net-(U6-6Y)") (class "Default")
      (node (ref "TP22") (pin "1") (pinfunction "1_1") (pintype "passive"))
      (node (ref "U6") (pin "12") (pinfunction "6Y_12") (pintype "passive"))
    )
  )
)
